# PWR.net
KiCad netlist of a schematic drawn in Altium Designer
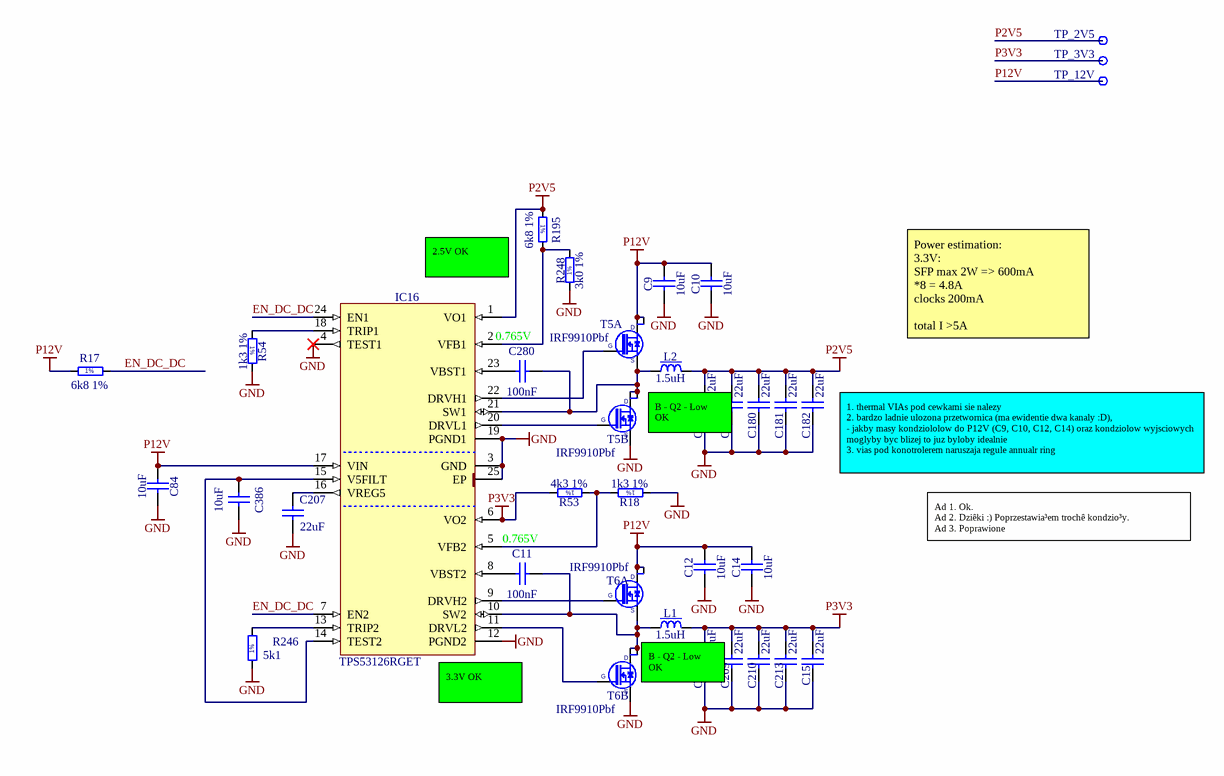
[diagram p0: PWR.SchDoc]

(export (version "E")
  (design (tool "Eeschema 10.0.6"))
  (components
    (comp (ref "C9")
      (value "10uF")
      (footprint "CAPC2012X135N")
      (description "Non-polarised capacitor")
      (fields
        (field (name "PART NUMBER") "CC0805_10UF_10V_10%_X7R")
        (field (name "VOLTAGE") "10V")
        (field (name "AUTHOR") "CERN DEM JLC")
      )
      (libsource (lib "Capacitors") (part "Capacitor - non polarized"))
    )
    (comp (ref "C10")
      (value "10uF")
      (footprint "CAPC2012X135N")
      (description "Non-polarised capacitor")
      (fields
        (field (name "PART NUMBER") "CC0805_10UF_10V_10%_X7R")
        (field (name "VOLTAGE") "10V")
        (field (name "AUTHOR") "CERN DEM JLC")
      )
      (libsource (lib "Capacitors") (part "Capacitor - non polarized"))
    )
    (comp (ref "C11")
      (value "100nF")
      (footprint "CAPC1005X55N")
      (description "Non-polarised capacitor")
      (fields
        (field (name "PART NUMBER") "CC0402_100NF_16V_10%_X7R")
        (field (name "VOLTAGE") "16V")
        (field (name "AUTHOR") "CERN DEM JLC")
      )
      (libsource (lib "Capacitors") (part "Capacitor - non polarized"))
    )
    (comp (ref "C12")
      (value "10uF")
      (footprint "CAPC2012X135N")
      (description "Non-polarised capacitor")
      (fields
        (field (name "PART NUMBER") "CC0805_10UF_10V_10%_X7R")
        (field (name "VOLTAGE") "10V")
        (field (name "AUTHOR") "CERN DEM JLC")
      )
      (libsource (lib "Capacitors") (part "Capacitor - non polarized"))
    )
    (comp (ref "C14")
      (value "10uF")
      (footprint "CAPC2012X135N")
      (description "Non-polarised capacitor")
      (fields
        (field (name "PART NUMBER") "CC0805_10UF_10V_10%_X7R")
        (field (name "VOLTAGE") "10V")
        (field (name "AUTHOR") "CERN DEM JLC")
      )
      (libsource (lib "Capacitors") (part "Capacitor - non polarized"))
    )
    (comp (ref "C15")
      (value "22uF")
      (footprint "CAPC3216X180N")
      (description "Non-polarised capacitor")
      (fields
        (field (name "PART NUMBER") "CC1206_22UF_10V_10%_X7R")
        (field (name "VOLTAGE") "10V")
        (field (name "AUTHOR") "CERN DEM JLC")
      )
      (libsource (lib "Capacitors") (part "Capacitor - non polarized"))
    )
    (comp (ref "C84")
      (value "10uF")
      (footprint "CAPC2012X135N")
      (description "Non-polarised capacitor")
      (fields
        (field (name "PART NUMBER") "CC0805_10UF_10V_10%_X7R")
        (field (name "VOLTAGE") "10V")
        (field (name "AUTHOR") "CERN DEM JLC")
      )
      (libsource (lib "Capacitors") (part "Capacitor - non polarized"))
    )
    (comp (ref "C176")
      (value "22uF")
      (footprint "CAPC3216X180N")
      (description "Non-polarised capacitor")
      (fields
        (field (name "PART NUMBER") "CC1206_22UF_10V_10%_X7R")
        (field (name "VOLTAGE") "10V")
        (field (name "AUTHOR") "CERN DEM JLC")
      )
      (libsource (lib "Capacitors") (part "Capacitor - non polarized"))
    )
    (comp (ref "C179")
      (value "22uF")
      (footprint "CAPC3216X180N")
      (description "Non-polarised capacitor")
      (fields
        (field (name "PART NUMBER") "CC1206_22UF_10V_10%_X7R")
        (field (name "VOLTAGE") "10V")
        (field (name "AUTHOR") "CERN DEM JLC")
      )
      (libsource (lib "Capacitors") (part "Capacitor - non polarized"))
    )
    (comp (ref "C180")
      (value "22uF")
      (footprint "CAPC3216X180N")
      (description "Non-polarised capacitor")
      (fields
        (field (name "PART NUMBER") "CC1206_22UF_10V_10%_X7R")
        (field (name "VOLTAGE") "10V")
        (field (name "AUTHOR") "CERN DEM JLC")
      )
      (libsource (lib "Capacitors") (part "Capacitor - non polarized"))
    )
    (comp (ref "C181")
      (value "22uF")
      (footprint "CAPC3216X180N")
      (description "Non-polarised capacitor")
      (fields
        (field (name "PART NUMBER") "CC1206_22UF_10V_10%_X7R")
        (field (name "VOLTAGE") "10V")
        (field (name "AUTHOR") "CERN DEM JLC")
      )
      (libsource (lib "Capacitors") (part "Capacitor - non polarized"))
    )
    (comp (ref "C182")
      (value "22uF")
      (footprint "CAPC3216X180N")
      (description "Non-polarised capacitor")
      (fields
        (field (name "PART NUMBER") "CC1206_22UF_10V_10%_X7R")
        (field (name "VOLTAGE") "10V")
        (field (name "AUTHOR") "CERN DEM JLC")
      )
      (libsource (lib "Capacitors") (part "Capacitor - non polarized"))
    )
    (comp (ref "C207")
      (value "22uF")
      (footprint "CAPC3216X180N")
      (description "Non-polarised capacitor")
      (fields
        (field (name "PART NUMBER") "CC1206_22UF_10V_10%_X7R")
        (field (name "VOLTAGE") "10V")
        (field (name "AUTHOR") "CERN DEM JLC")
      )
      (libsource (lib "Capacitors") (part "Capacitor - non polarized"))
    )
    (comp (ref "C208")
      (value "22uF")
      (footprint "CAPC3216X180N")
      (description "Non-polarised capacitor")
      (fields
        (field (name "PART NUMBER") "CC1206_22UF_10V_10%_X7R")
        (field (name "VOLTAGE") "10V")
        (field (name "AUTHOR") "CERN DEM JLC")
      )
      (libsource (lib "Capacitors") (part "Capacitor - non polarized"))
    )
    (comp (ref "C209")
      (value "22uF")
      (footprint "CAPC3216X180N")
      (description "Non-polarised capacitor")
      (fields
        (field (name "PART NUMBER") "CC1206_22UF_10V_10%_X7R")
        (field (name "VOLTAGE") "10V")
        (field (name "AUTHOR") "CERN DEM JLC")
      )
      (libsource (lib "Capacitors") (part "Capacitor - non polarized"))
    )
    (comp (ref "C210")
      (value "22uF")
      (footprint "CAPC3216X180N")
      (description "Non-polarised capacitor")
      (fields
        (field (name "PART NUMBER") "CC1206_22UF_10V_10%_X7R")
        (field (name "VOLTAGE") "10V")
        (field (name "AUTHOR") "CERN DEM JLC")
      )
      (libsource (lib "Capacitors") (part "Capacitor - non polarized"))
    )
    (comp (ref "C213")
      (value "22uF")
      (footprint "CAPC3216X180N")
      (description "Non-polarised capacitor")
      (fields
        (field (name "PART NUMBER") "CC1206_22UF_10V_10%_X7R")
        (field (name "VOLTAGE") "10V")
        (field (name "AUTHOR") "CERN DEM JLC")
      )
      (libsource (lib "Capacitors") (part "Capacitor - non polarized"))
    )
    (comp (ref "C280")
      (value "100nF")
      (footprint "CAPC1005X55N")
      (description "Non-polarised capacitor")
      (fields
        (field (name "PART NUMBER") "CC0402_100NF_16V_10%_X7R")
        (field (name "VOLTAGE") "16V")
        (field (name "AUTHOR") "CERN DEM JLC")
      )
      (libsource (lib "Capacitors") (part "Capacitor - non polarized"))
    )
    (comp (ref "C386")
      (value "10uF")
      (footprint "CAPC2012X135N")
      (description "Non-polarised capacitor")
      (fields
        (field (name "PART NUMBER") "CC0805_10UF_10V_10%_X7R")
        (field (name "VOLTAGE") "10V")
        (field (name "AUTHOR") "CERN DEM JLC")
      )
      (libsource (lib "Capacitors") (part "Capacitor - non polarized"))
    )
    (comp (ref "IC16")
      (value "TPS53126RGET")
      (footprint "QFN50P400X400X100-25N-S255")
      (description "Dual Synchronous Step-Down Controller For Low Voltage Power Rails")
      (fields (field (name "MANUFACTURER") "TEXAS INSTRUMENTS") (field (name "AUTHOR") "CERN DEM JLC"))
      (libsource (lib "ICs And Semiconductors") (part "TPS53126RGET"))
    )
    (comp (ref "L1")
      (value "1.5uH")
      (footprint "INDM6965X300N")
      (description "Inductor With Magnetic core")
      (fields
        (field (name "PART NUMBER") "IND2525_1.5UH_20%_VISHAY_IHLP-2525CZ")
        (field (name "POWER") "9A")
        (field (name "AUTHOR") "CERN DEM JLC")
      )
      (libsource (lib "Inductors & Transformers") (part "Inductor With Magnetic core"))
    )
    (comp (ref "L2")
      (value "1.5uH")
      (footprint "INDM6965X300N")
      (description "Inductor With Magnetic core")
      (fields
        (field (name "PART NUMBER") "IND2525_1.5UH_20%_VISHAY_IHLP-2525CZ")
        (field (name "POWER") "9A")
        (field (name "AUTHOR") "CERN DEM JLC")
      )
      (libsource (lib "Inductors & Transformers") (part "Inductor With Magnetic core"))
    )
    (comp (ref "R17")
      (value "6k8 1%")
      (footprint "RESC1608X55N")
      (description "Resistor - 1%")
      (fields
        (field (name "PART NUMBER") "R0603_6K8_1%_0.1W_100PPM")
        (field (name "POWER") "0.1W")
        (field (name "AUTHOR") "CERN DEM JLC")
      )
      (libsource (lib "Resistors") (part "Resistor - 1%"))
    )
    (comp (ref "R18")
      (value "1k3 1%")
      (footprint "RESC1608X55N")
      (description "Resistor - 1%")
      (fields
        (field (name "PART NUMBER") "R0603_1K3_1%_0.1W_100PPM")
        (field (name "POWER") "0.1W")
        (field (name "AUTHOR") "CERN DEM JLC")
      )
      (libsource (lib "Resistors") (part "Resistor - 1%"))
    )
    (comp (ref "R53")
      (value "4k3 1%")
      (footprint "RESC1608X55N")
      (description "Resistor - 1%")
      (fields
        (field (name "PART NUMBER") "R0603_4K3_1%_0.1W_100PPM")
        (field (name "POWER") "0.1W")
        (field (name "AUTHOR") "CERN DEM JLC")
      )
      (libsource (lib "Resistors") (part "Resistor - 1%"))
    )
    (comp (ref "R54")
      (value "1k3 1%")
      (footprint "RESC1608X55N")
      (description "Resistor - 1%")
      (fields
        (field (name "PART NUMBER") "R0603_1K3_1%_0.1W_100PPM")
        (field (name "POWER") "0.1W")
        (field (name "AUTHOR") "CERN DEM JLC")
      )
      (libsource (lib "Resistors") (part "Resistor - 1%"))
    )
    (comp (ref "R195")
      (value "6k8 1%")
      (footprint "RESC1608X55N")
      (description "Resistor - 1%")
      (fields
        (field (name "PART NUMBER") "R0603_6K8_1%_0.1W_100PPM")
        (field (name "POWER") "0.1W")
        (field (name "AUTHOR") "CERN DEM JLC")
      )
      (libsource (lib "Resistors") (part "Resistor - 1%"))
    )
    (comp (ref "R246")
      (value "5k1")
      (footprint "RESC1608X55N")
      (description "Resistor - 1%")
      (fields
        (field (name "PART NUMBER") "R0603_5K1_1%_0.1W_100PPM")
        (field (name "POWER") "0.1W")
        (field (name "AUTHOR") "CERN DEM JLC")
      )
      (libsource (lib "Resistors") (part "Resistor - 1%"))
    )
    (comp (ref "R248")
      (value "3k0 1%")
      (footprint "RESC1608X55N")
      (description "Resistor - 1%")
      (fields
        (field (name "PART NUMBER") "R0603_3K_1%_0.1W_100PPM")
        (field (name "POWER") "0.1W")
        (field (name "AUTHOR") "CERN DEM JLC")
      )
      (libsource (lib "Resistors") (part "Resistor - 1%"))
    )
    (comp (ref "T5")
      (value "IRF9910Pbf")
      (footprint "SOIC127P600X175-8N")
      (description "Dual SO-8 MOSFET For POL Cconverter")
      (fields (field (name "MANUFACTURER") "INTERNATIONAL RECTIFIER") (field (name "AUTHOR") "CERN DEM JLC"))
      (libsource (lib "ICs And Semiconductors") (part "IRF9910"))
    )
    (comp (ref "T6")
      (value "IRF9910Pbf")
      (footprint "SOIC127P600X175-8N")
      (description "Dual SO-8 MOSFET For POL Cconverter")
      (fields (field (name "MANUFACTURER") "INTERNATIONAL RECTIFIER") (field (name "AUTHOR") "CERN DEM JLC"))
      (libsource (lib "ICs And Semiconductors") (part "IRF9910"))
    )
    (comp (ref "TP_2V5")
      (value "Test Point")
      (footprint "TPS127")
      (fields (field (name "PART NUMBER") "SMD_PAD_1.27X1.27MM") (field (name "AUTHOR") "CERN DEM JLC"))
      (libsource (lib "Eletro-mechanical") (part "Test Point"))
    )
    (comp (ref "TP_3V3")
      (value "Test Point")
      (footprint "TPS127")
      (fields (field (name "PART NUMBER") "SMD_PAD_1.27X1.27MM") (field (name "AUTHOR") "CERN DEM JLC"))
      (libsource (lib "Eletro-mechanical") (part "Test Point"))
    )
    (comp (ref "TP_12V")
      (value "Test Point")
      (footprint "TPS127")
      (fields (field (name "PART NUMBER") "SMD_PAD_1.27X1.27MM") (field (name "AUTHOR") "CERN DEM JLC"))
      (libsource (lib "Eletro-mechanical") (part "Test Point"))
    )
  )
  (nets
    (net (code "1") (name "/EN_DC_DC") (class "Default")
      (node (ref "IC16") (pin "24") (pinfunction "EN1_24") (pintype "input"))
      (node (ref "IC16") (pin "7") (pinfunction "EN2_7") (pintype "input"))
      (node (ref "R17") (pin "2") (pinfunction "2_2") (pintype "passive"))
    )
    (net (code "2") (name "GND") (class "Default")
      (node (ref "C10") (pin "1") (pinfunction "1_1") (pintype "passive"))
      (node (ref "C12") (pin "1") (pinfunction "1_1") (pintype "passive"))
      (node (ref "C14") (pin "1") (pinfunction "1_1") (pintype "passive"))
      (node (ref "C15") (pin "1") (pinfunction "1_1") (pintype "passive"))
      (node (ref "C176") (pin "1") (pinfunction "1_1") (pintype "passive"))
      (node (ref "C179") (pin "1") (pinfunction "1_1") (pintype "passive"))
      (node (ref "C180") (pin "1") (pinfunction "1_1") (pintype "passive"))
      (node (ref "C181") (pin "1") (pinfunction "1_1") (pintype "passive"))
      (node (ref "C182") (pin "1") (pinfunction "1_1") (pintype "passive"))
      (node (ref "C207") (pin "1") (pinfunction "1_1") (pintype "passive"))
      (node (ref "C208") (pin "1") (pinfunction "1_1") (pintype "passive"))
      (node (ref "C209") (pin "1") (pinfunction "1_1") (pintype "passive"))
      (node (ref "C210") (pin "1") (pinfunction "1_1") (pintype "passive"))
      (node (ref "C213") (pin "1") (pinfunction "1_1") (pintype "passive"))
      (node (ref "C386") (pin "1") (pinfunction "1_1") (pintype "passive"))
      (node (ref "C84") (pin "2") (pinfunction "2_2") (pintype "passive"))
      (node (ref "C9") (pin "1") (pinfunction "1_1") (pintype "passive"))
      (node (ref "IC16") (pin "12") (pinfunction "PGND2_12") (pintype "power_in"))
      (node (ref "IC16") (pin "19") (pinfunction "PGND1_19") (pintype "power_in"))
      (node (ref "IC16") (pin "25") (pinfunction "EP_25") (pintype "power_in"))
      (node (ref "IC16") (pin "3") (pinfunction "GND_3") (pintype "power_in"))
      (node (ref "IC16") (pin "4") (pinfunction "TEST1_4") (pintype "output"))
      (node (ref "R18") (pin "1") (pinfunction "1_1") (pintype "passive"))
      (node (ref "R246") (pin "1") (pinfunction "1_1") (pintype "passive"))
      (node (ref "R248") (pin "1") (pinfunction "1_1") (pintype "passive"))
      (node (ref "R54") (pin "2") (pinfunction "2_2") (pintype "passive"))
      (node (ref "T5") (pin "1") (pinfunction "S_1") (pintype "passive"))
      (node (ref "T6") (pin "1") (pinfunction "S_1") (pintype "passive"))
    )
    (net (code "3") (name "Net-(IC16-DRVH1)") (class "Default")
      (node (ref "IC16") (pin "22") (pinfunction "DRVH1_22") (pintype "output"))
      (node (ref "T5") (pin "4") (pinfunction "G_4") (pintype "passive"))
    )
    (net (code "4") (name "Net-(IC16-DRVH2)") (class "Default")
      (node (ref "IC16") (pin "9") (pinfunction "DRVH2_9") (pintype "output"))
      (node (ref "T6") (pin "4") (pinfunction "G_4") (pintype "passive"))
    )
    (net (code "5") (name "Net-(IC16-DRVL1)") (class "Default")
      (node (ref "IC16") (pin "20") (pinfunction "DRVL1_20") (pintype "output"))
      (node (ref "T5") (pin "2") (pinfunction "G_2") (pintype "passive"))
    )
    (net (code "6") (name "Net-(IC16-DRVL2)") (class "Default")
      (node (ref "IC16") (pin "11") (pinfunction "DRVL2_11") (pintype "output"))
      (node (ref "T6") (pin "2") (pinfunction "G_2") (pintype "passive"))
    )
    (net (code "7") (name "Net-(IC16-SW1)") (class "Default")
      (node (ref "C280") (pin "1") (pinfunction "1_1") (pintype "passive"))
      (node (ref "IC16") (pin "21") (pinfunction "SW1_21") (pintype "bidirectional"))
      (node (ref "L2") (pin "1") (pinfunction "1_1") (pintype "passive"))
      (node (ref "T5") (pin "3") (pinfunction "S_3") (pintype "passive"))
      (node (ref "T5") (pin "7") (pinfunction "D_7") (pintype "passive"))
      (node (ref "T5") (pin "8") (pinfunction "D_8") (pintype "passive"))
    )
    (net (code "8") (name "Net-(IC16-SW2)") (class "Default")
      (node (ref "C11") (pin "1") (pinfunction "1_1") (pintype "passive"))
      (node (ref "IC16") (pin "10") (pinfunction "SW2_10") (pintype "bidirectional"))
      (node (ref "L1") (pin "1") (pinfunction "1_1") (pintype "passive"))
      (node (ref "T6") (pin "3") (pinfunction "S_3") (pintype "passive"))
      (node (ref "T6") (pin "7") (pinfunction "D_7") (pintype "passive"))
      (node (ref "T6") (pin "8") (pinfunction "D_8") (pintype "passive"))
    )
    (net (code "9") (name "Net-(IC16-TEST2)") (class "Default")
      (node (ref "C386") (pin "2") (pinfunction "2_2") (pintype "passive"))
      (node (ref "IC16") (pin "14") (pinfunction "TEST2_14") (pintype "input"))
      (node (ref "IC16") (pin "15") (pinfunction "V5FILT_15") (pintype "input"))
    )
    (net (code "10") (name "Net-(IC16-TRIP1)") (class "Default")
      (node (ref "IC16") (pin "18") (pinfunction "TRIP1_18") (pintype "input"))
      (node (ref "R54") (pin "1") (pinfunction "1_1") (pintype "passive"))
    )
    (net (code "11") (name "Net-(IC16-TRIP2)") (class "Default")
      (node (ref "IC16") (pin "13") (pinfunction "TRIP2_13") (pintype "input"))
      (node (ref "R246") (pin "2") (pinfunction "2_2") (pintype "passive"))
    )
    (net (code "12") (name "Net-(IC16-VBST1)") (class "Default")
      (node (ref "C280") (pin "2") (pinfunction "2_2") (pintype "passive"))
      (node (ref "IC16") (pin "23") (pinfunction "VBST1_23") (pintype "input"))
    )
    (net (code "13") (name "Net-(IC16-VBST2)") (class "Default")
      (node (ref "C11") (pin "2") (pinfunction "2_2") (pintype "passive"))
      (node (ref "IC16") (pin "8") (pinfunction "VBST2_8") (pintype "input"))
    )
    (net (code "14") (name "Net-(IC16-VFB1)") (class "Default")
      (node (ref "IC16") (pin "2") (pinfunction "VFB1_2") (pintype "input"))
      (node (ref "R195") (pin "2") (pinfunction "2_2") (pintype "passive"))
      (node (ref "R248") (pin "2") (pinfunction "2_2") (pintype "passive"))
    )
    (net (code "15") (name "Net-(IC16-VFB2)") (class "Default")
      (node (ref "IC16") (pin "5") (pinfunction "VFB2_5") (pintype "input"))
      (node (ref "R18") (pin "2") (pinfunction "2_2") (pintype "passive"))
      (node (ref "R53") (pin "1") (pinfunction "1_1") (pintype "passive"))
    )
    (net (code "16") (name "Net-(IC16-VREG5)") (class "Default")
      (node (ref "C207") (pin "2") (pinfunction "2_2") (pintype "passive"))
      (node (ref "IC16") (pin "16") (pinfunction "VREG5_16") (pintype "output"))
    )
    (net (code "17") (name "P2V5") (class "Default")
      (node (ref "C176") (pin "2") (pinfunction "2_2") (pintype "passive"))
      (node (ref "C179") (pin "2") (pinfunction "2_2") (pintype "passive"))
      (node (ref "C180") (pin "2") (pinfunction "2_2") (pintype "passive"))
      (node (ref "C181") (pin "2") (pinfunction "2_2") (pintype "passive"))
      (node (ref "C182") (pin "2") (pinfunction "2_2") (pintype "passive"))
      (node (ref "IC16") (pin "1") (pinfunction "VO1_1") (pintype "input"))
      (node (ref "L2") (pin "2") (pinfunction "2_2") (pintype "passive"))
      (node (ref "R195") (pin "1") (pinfunction "1_1") (pintype "passive"))
      (node (ref "TP_2V5") (pin "1") (pinfunction "1_1") (pintype "bidirectional"))
    )
    (net (code "18") (name "P3V3") (class "Default")
      (node (ref "C15") (pin "2") (pinfunction "2_2") (pintype "passive"))
      (node (ref "C208") (pin "2") (pinfunction "2_2") (pintype "passive"))
      (node (ref "C209") (pin "2") (pinfunction "2_2") (pintype "passive"))
      (node (ref "C210") (pin "2") (pinfunction "2_2") (pintype "passive"))
      (node (ref "C213") (pin "2") (pinfunction "2_2") (pintype "passive"))
      (node (ref "IC16") (pin "6") (pinfunction "VO2_6") (pintype "input"))
      (node (ref "L1") (pin "2") (pinfunction "2_2") (pintype "passive"))
      (node (ref "R53") (pin "2") (pinfunction "2_2") (pintype "passive"))
      (node (ref "TP_3V3") (pin "1") (pinfunction "1_1") (pintype "bidirectional"))
    )
    (net (code "19") (name "P12V") (class "Default")
      (node (ref "C10") (pin "2") (pinfunction "2_2") (pintype "passive"))
      (node (ref "C12") (pin "2") (pinfunction "2_2") (pintype "passive"))
      (node (ref "C14") (pin "2") (pinfunction "2_2") (pintype "passive"))
      (node (ref "C84") (pin "1") (pinfunction "1_1") (pintype "passive"))
      (node (ref "C9") (pin "2") (pinfunction "2_2") (pintype "passive"))
      (node (ref "IC16") (pin "17") (pinfunction "VIN_17") (pintype "input"))
      (node (ref "R17") (pin "1") (pinfunction "1_1") (pintype "passive"))
      (node (ref "T5") (pin "5") (pinfunction "D_5") (pintype "passive"))
      (node (ref "T5") (pin "6") (pinfunction "D_6") (pintype "passive"))
      (node (ref "T6") (pin "5") (pinfunction "D_5") (pintype "passive"))
      (node (ref "T6") (pin "6") (pinfunction "D_6") (pintype "passive"))
      (node (ref "TP_12V") (pin "1") (pinfunction "1_1") (pintype "bidirectional"))
    )
  )
)
